# ece411_t2_schematic_FINAL.net
KiCad netlist of a schematic drawn in EAGLE
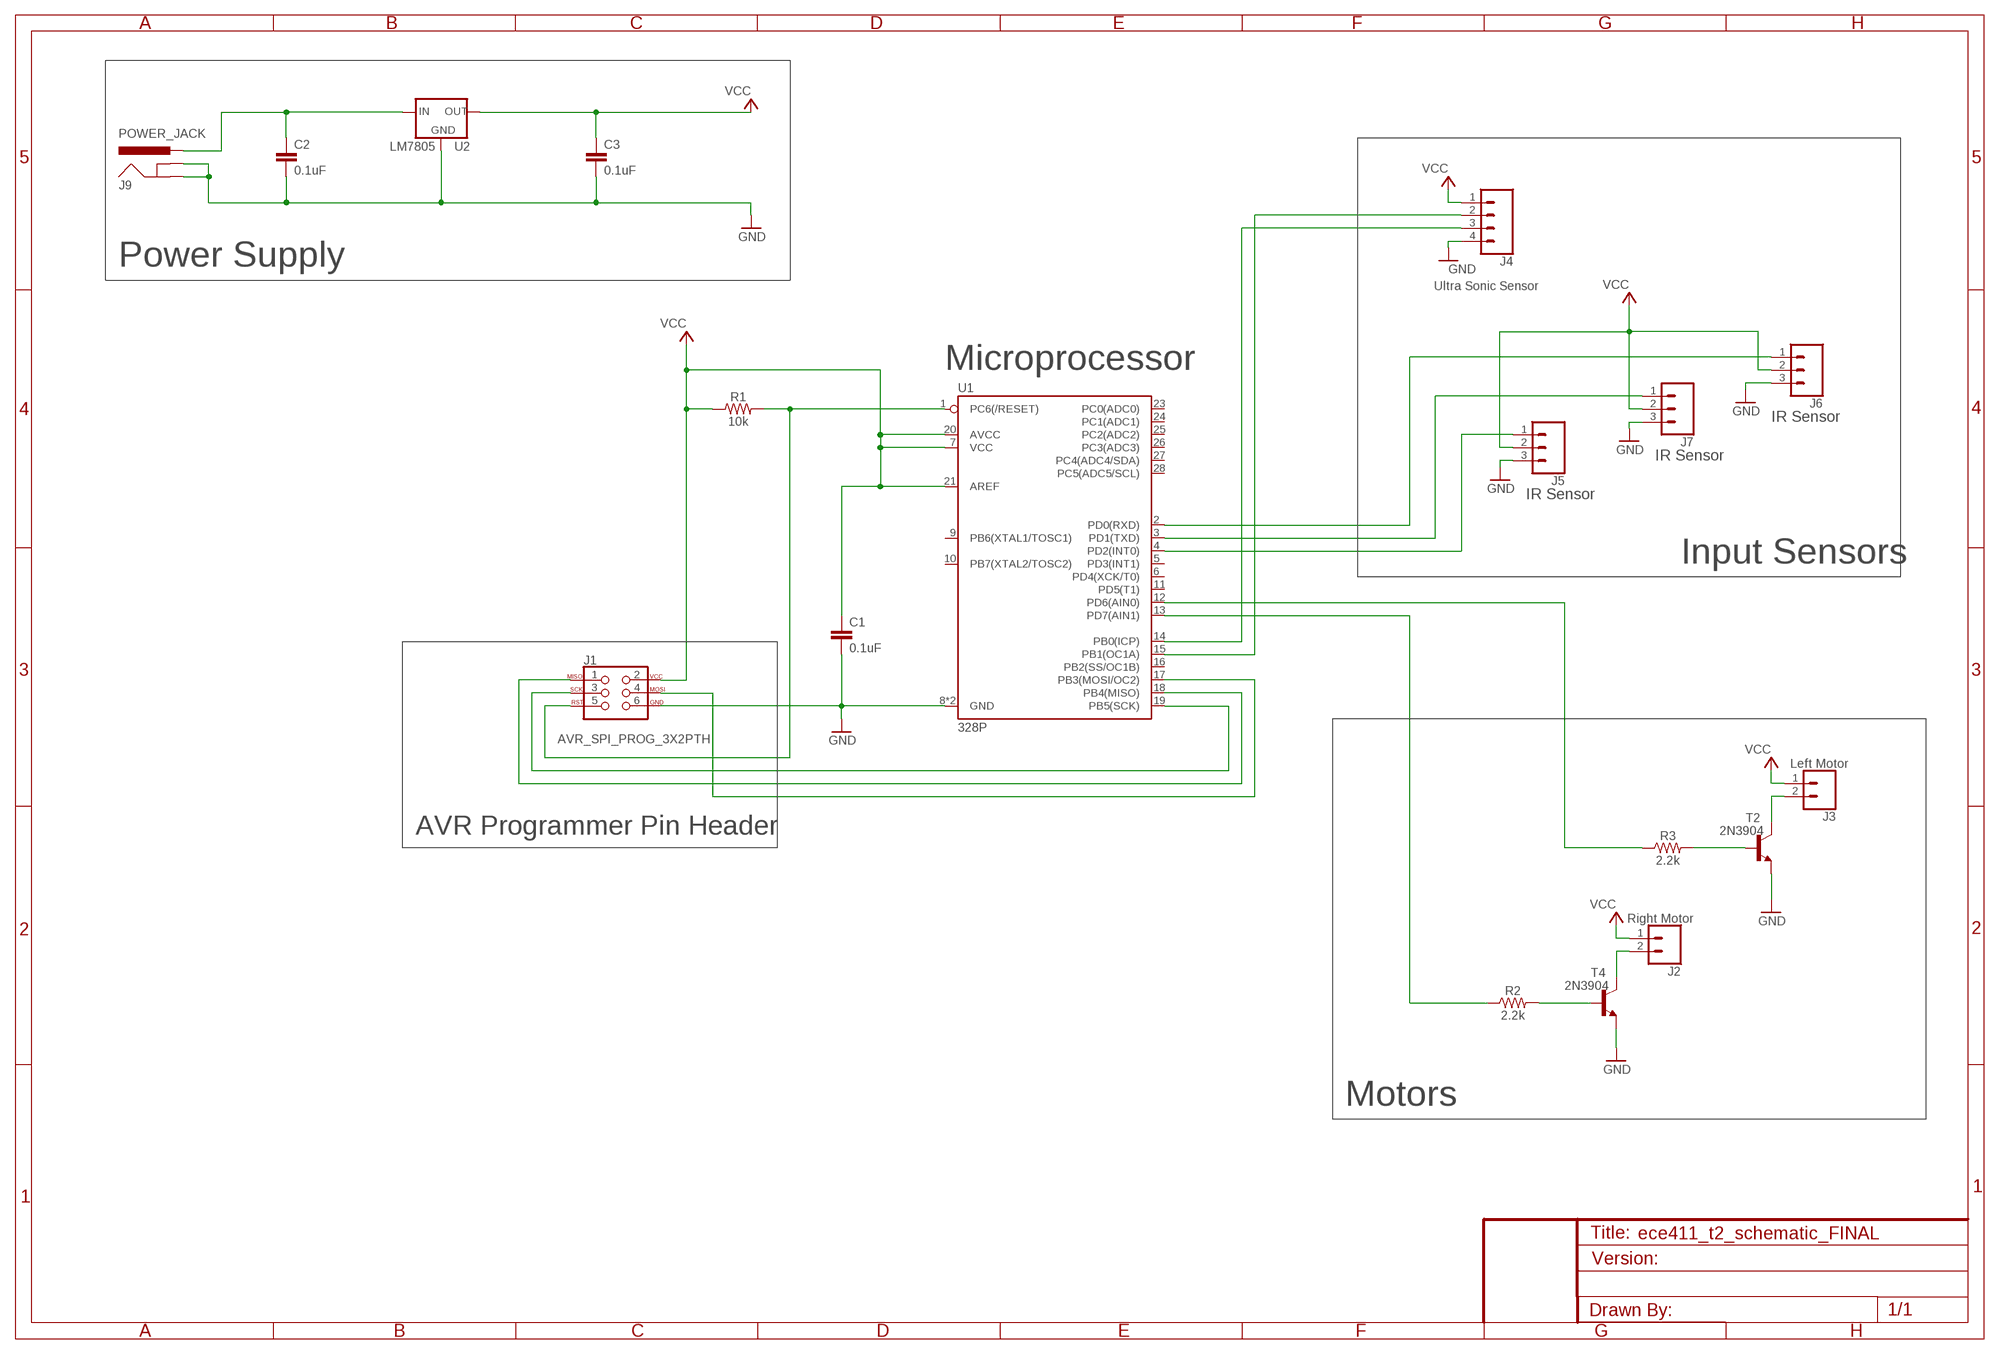
[diagram p0: schematic, sheet 1]

(export (version "E")
  (design (tool "Eeschema 10.0.6"))
  (components
    (comp (ref "C1")
      (value "0.1uF")
      (footprint "eagle-import:0402")
      (libsource (lib "eagle-import") (part "0.1UF-0402-6.3V-10%-X7R"))
    )
    (comp (ref "C2")
      (value "0.1uF")
      (footprint "eagle-import:0402")
      (libsource (lib "eagle-import") (part "0.1UF-0402-6.3V-10%-X7R"))
    )
    (comp (ref "C3")
      (value "0.1uF")
      (footprint "eagle-import:0402")
      (libsource (lib "eagle-import") (part "0.1UF-0402-6.3V-10%-X7R"))
    )
    (comp (ref "J1")
      (value "AVR_SPI_PROG_3X2PTH")
      (footprint "eagle-import:2X3")
      (libsource (lib "eagle-import") (part "AVR_SPI_PROG_3X2PTH"))
    )
    (comp (ref "J2")
      (value "Right Motor")
      (footprint "eagle-import:1X02")
      (libsource (lib "eagle-import") (part "CONN_02"))
    )
    (comp (ref "J3")
      (value "Left Motor")
      (footprint "eagle-import:1X02")
      (libsource (lib "eagle-import") (part "CONN_02"))
    )
    (comp (ref "J4")
      (value "Ultra Sonic Sensor")
      (footprint "eagle-import:1X04")
      (libsource (lib "eagle-import") (part "CONN_04"))
    )
    (comp (ref "J5")
      (value "455-1750-1-ND")
      (footprint "eagle-import:1X03")
      (libsource (lib "eagle-import") (part "CONN_03"))
    )
    (comp (ref "J6")
      (value "455-1750-1-ND")
      (footprint "eagle-import:1X03")
      (libsource (lib "eagle-import") (part "CONN_03"))
    )
    (comp (ref "J7")
      (value "455-1750-1-ND")
      (footprint "eagle-import:1X03")
      (libsource (lib "eagle-import") (part "CONN_03"))
    )
    (comp (ref "J9")
      (value "POWER_JACK")
      (footprint "eagle-import:POWER_JACK_PTH")
      (libsource (lib "eagle-import") (part "POWER_JACK"))
    )
    (comp (ref "R1")
      (value "10k")
      (footprint "eagle-import:0402")
      (libsource (lib "eagle-import") (part "10KOHM-0402-1/16W-1%"))
    )
    (comp (ref "R2")
      (value "2.2k")
      (footprint "eagle-import:0603")
      (libsource (lib "eagle-import") (part "2.2KOHM-0603-1/10W-1%"))
    )
    (comp (ref "R3")
      (value "2.2k")
      (footprint "eagle-import:0603")
      (libsource (lib "eagle-import") (part "2.2KOHM-0603-1/10W-1%"))
    )
    (comp (ref "T2")
      (value "2N3904")
      (footprint "eagle-import:TO92")
      (libsource (lib "eagle-import") (part "2N3904"))
    )
    (comp (ref "T4")
      (value "2N3904")
      (footprint "eagle-import:TO92")
      (libsource (lib "eagle-import") (part "2N3904"))
    )
    (comp (ref "U1")
      (value "328P")
      (footprint "eagle-import:DIP28")
      (libsource (lib "eagle-import") (part "ATMEGA328P_PDIP"))
    )
    (comp (ref "U2")
      (value "LM7805")
      (footprint "eagle-import:TO-220-ALT")
      (libsource (lib "eagle-import") (part "V_REG_78XX-TO-220"))
    )
  )
  (nets
    (net (code "1") (name "GND") (class "Default")
      (node (ref "C1") (pin "2") (pinfunction "2_2") (pintype "passive"))
      (node (ref "C2") (pin "2") (pinfunction "2_2") (pintype "passive"))
      (node (ref "C3") (pin "2") (pinfunction "2_2") (pintype "passive"))
      (node (ref "J1") (pin "6") (pinfunction "6_6") (pintype "passive"))
      (node (ref "J4") (pin "4") (pinfunction "4_4") (pintype "passive"))
      (node (ref "J5") (pin "3") (pinfunction "3_3") (pintype "passive"))
      (node (ref "J6") (pin "3") (pinfunction "3_3") (pintype "passive"))
      (node (ref "J7") (pin "3") (pinfunction "3_3") (pintype "passive"))
      (node (ref "J9") (pin "GND") (pinfunction "GND_GND") (pintype "bidirectional"))
      (node (ref "J9") (pin "GNDBREAK") (pinfunction "GNDBREAK_GNDBREAK") (pintype "bidirectional"))
      (node (ref "T2") (pin "3") (pinfunction "E_3") (pintype "passive"))
      (node (ref "T4") (pin "3") (pinfunction "E_3") (pintype "passive"))
      (node (ref "U1") (pin "22") (pinfunction "GND_22") (pintype "bidirectional"))
      (node (ref "U1") (pin "8") (pinfunction "GND_8") (pintype "bidirectional"))
      (node (ref "U2") (pin "GND") (pinfunction "GND_GND") (pintype "input"))
    )
    (net (code "2") (name "Net-(C2-Pad1)") (class "Default")
      (node (ref "C2") (pin "1") (pinfunction "1_1") (pintype "passive"))
      (node (ref "J9") (pin "PWR") (pinfunction "PWR_PWR") (pintype "bidirectional"))
      (node (ref "U2") (pin "IN") (pinfunction "IN_IN") (pintype "input"))
    )
    (net (code "3") (name "Net-(T2-B)") (class "Default")
      (node (ref "R3") (pin "2") (pinfunction "2_2") (pintype "passive"))
      (node (ref "T2") (pin "2") (pinfunction "B_2") (pintype "passive"))
    )
    (net (code "4") (name "Net-(T2-C)") (class "Default")
      (node (ref "J3") (pin "2") (pinfunction "2_2") (pintype "passive"))
      (node (ref "T2") (pin "1") (pinfunction "C_1") (pintype "passive"))
    )
    (net (code "5") (name "Net-(T4-B)") (class "Default")
      (node (ref "R2") (pin "2") (pinfunction "2_2") (pintype "passive"))
      (node (ref "T4") (pin "2") (pinfunction "B_2") (pintype "passive"))
    )
    (net (code "6") (name "Net-(T4-C)") (class "Default")
      (node (ref "J2") (pin "2") (pinfunction "2_2") (pintype "passive"))
      (node (ref "T4") (pin "1") (pinfunction "C_1") (pintype "passive"))
    )
    (net (code "7") (name "Net-(U1-PB0(ICP))") (class "Default")
      (node (ref "J4") (pin "3") (pinfunction "3_3") (pintype "passive"))
      (node (ref "U1") (pin "14") (pinfunction "PB0(ICP)_14") (pintype "bidirectional"))
    )
    (net (code "8") (name "Net-(U1-PB1(OC1A))") (class "Default")
      (node (ref "J4") (pin "2") (pinfunction "2_2") (pintype "passive"))
      (node (ref "U1") (pin "15") (pinfunction "PB1(OC1A)_15") (pintype "bidirectional"))
    )
    (net (code "9") (name "Net-(U1-PB3(MOSI{slash}OC2))") (class "Default")
      (node (ref "J1") (pin "4") (pinfunction "4_4") (pintype "passive"))
      (node (ref "U1") (pin "17") (pinfunction "PB3(MOSI/OC2)_17") (pintype "bidirectional"))
    )
    (net (code "10") (name "Net-(U1-PB4(MISO))") (class "Default")
      (node (ref "J1") (pin "1") (pinfunction "1_1") (pintype "passive"))
      (node (ref "U1") (pin "18") (pinfunction "PB4(MISO)_18") (pintype "bidirectional"))
    )
    (net (code "11") (name "Net-(U1-PB5(SCK))") (class "Default")
      (node (ref "J1") (pin "3") (pinfunction "3_3") (pintype "passive"))
      (node (ref "U1") (pin "19") (pinfunction "PB5(SCK)_19") (pintype "bidirectional"))
    )
    (net (code "12") (name "Net-(U1-PC6({slash}RESET))") (class "Default")
      (node (ref "J1") (pin "5") (pinfunction "5_5") (pintype "passive"))
      (node (ref "R1") (pin "2") (pinfunction "2_2") (pintype "passive"))
      (node (ref "U1") (pin "1") (pinfunction "PC6(/RESET)_1") (pintype "bidirectional"))
    )
    (net (code "13") (name "Net-(U1-PD0(RXD))") (class "Default")
      (node (ref "J6") (pin "1") (pinfunction "1_1") (pintype "passive"))
      (node (ref "U1") (pin "2") (pinfunction "PD0(RXD)_2") (pintype "bidirectional"))
    )
    (net (code "14") (name "Net-(U1-PD1(TXD))") (class "Default")
      (node (ref "J7") (pin "1") (pinfunction "1_1") (pintype "passive"))
      (node (ref "U1") (pin "3") (pinfunction "PD1(TXD)_3") (pintype "bidirectional"))
    )
    (net (code "15") (name "Net-(U1-PD2(INT0))") (class "Default")
      (node (ref "J5") (pin "1") (pinfunction "1_1") (pintype "passive"))
      (node (ref "U1") (pin "4") (pinfunction "PD2(INT0)_4") (pintype "bidirectional"))
    )
    (net (code "16") (name "Net-(U1-PD6(AIN0))") (class "Default")
      (node (ref "R3") (pin "1") (pinfunction "1_1") (pintype "passive"))
      (node (ref "U1") (pin "12") (pinfunction "PD6(AIN0)_12") (pintype "bidirectional"))
    )
    (net (code "17") (name "Net-(U1-PD7(AIN1))") (class "Default")
      (node (ref "R2") (pin "1") (pinfunction "1_1") (pintype "passive"))
      (node (ref "U1") (pin "13") (pinfunction "PD7(AIN1)_13") (pintype "bidirectional"))
    )
    (net (code "18") (name "VCC") (class "Default")
      (node (ref "C1") (pin "1") (pinfunction "1_1") (pintype "passive"))
      (node (ref "C3") (pin "1") (pinfunction "1_1") (pintype "passive"))
      (node (ref "J1") (pin "2") (pinfunction "2_2") (pintype "passive"))
      (node (ref "J2") (pin "1") (pinfunction "1_1") (pintype "passive"))
      (node (ref "J3") (pin "1") (pinfunction "1_1") (pintype "passive"))
      (node (ref "J4") (pin "1") (pinfunction "1_1") (pintype "passive"))
      (node (ref "J5") (pin "2") (pinfunction "2_2") (pintype "passive"))
      (node (ref "J6") (pin "2") (pinfunction "2_2") (pintype "passive"))
      (node (ref "J7") (pin "2") (pinfunction "2_2") (pintype "passive"))
      (node (ref "R1") (pin "1") (pinfunction "1_1") (pintype "passive"))
      (node (ref "U1") (pin "20") (pinfunction "AVCC_20") (pintype "bidirectional"))
      (node (ref "U1") (pin "21") (pinfunction "AREF_21") (pintype "bidirectional"))
      (node (ref "U1") (pin "7") (pinfunction "VCC_7") (pintype "bidirectional"))
      (node (ref "U2") (pin "OUT") (pinfunction "OUT_OUT") (pintype "passive"))
    )
    (net (code "19") (name "unconnected-(U1-PB2(SS{slash}OC1B)-Pad16)") (class "Default")
      (node (ref "U1") (pin "16") (pinfunction "PB2(SS/OC1B)_16") (pintype "bidirectional"))
    )
    (net (code "20") (name "unconnected-(U1-PB6(XTAL1{slash}TOSC1)-Pad9)") (class "Default")
      (node (ref "U1") (pin "9") (pinfunction "PB6(XTAL1/TOSC1)_9") (pintype "bidirectional"))
    )
    (net (code "21") (name "unconnected-(U1-PB7(XTAL2{slash}TOSC2)-Pad10)") (class "Default")
      (node (ref "U1") (pin "10") (pinfunction "PB7(XTAL2/TOSC2)_10") (pintype "bidirectional"))
    )
    (net (code "22") (name "unconnected-(U1-PC0(ADC0)-Pad23)") (class "Default")
      (node (ref "U1") (pin "23") (pinfunction "PC0(ADC0)_23") (pintype "bidirectional"))
    )
    (net (code "23") (name "unconnected-(U1-PC1(ADC1)-Pad24)") (class "Default")
      (node (ref "U1") (pin "24") (pinfunction "PC1(ADC1)_24") (pintype "bidirectional"))
    )
    (net (code "24") (name "unconnected-(U1-PC2(ADC2)-Pad25)") (class "Default")
      (node (ref "U1") (pin "25") (pinfunction "PC2(ADC2)_25") (pintype "bidirectional"))
    )
    (net (code "25") (name "unconnected-(U1-PC3(ADC3)-Pad26)") (class "Default")
      (node (ref "U1") (pin "26") (pinfunction "PC3(ADC3)_26") (pintype "bidirectional"))
    )
    (net (code "26") (name "unconnected-(U1-PC4(ADC4{slash}SDA)-Pad27)") (class "Default")
      (node (ref "U1") (pin "27") (pinfunction "PC4(ADC4/SDA)_27") (pintype "bidirectional"))
    )
    (net (code "27") (name "unconnected-(U1-PC5(ADC5{slash}SCL)-Pad28)") (class "Default")
      (node (ref "U1") (pin "28") (pinfunction "PC5(ADC5/SCL)_28") (pintype "bidirectional"))
    )
    (net (code "28") (name "unconnected-(U1-PD3(INT1)-Pad5)") (class "Default")
      (node (ref "U1") (pin "5") (pinfunction "PD3(INT1)_5") (pintype "bidirectional"))
    )
    (net (code "29") (name "unconnected-(U1-PD4(XCK{slash}T0)-Pad6)") (class "Default")
      (node (ref "U1") (pin "6") (pinfunction "PD4(XCK/T0)_6") (pintype "bidirectional"))
    )
    (net (code "30") (name "unconnected-(U1-PD5(T1)-Pad11)") (class "Default")
      (node (ref "U1") (pin "11") (pinfunction "PD5(T1)_11") (pintype "bidirectional"))
    )
  )
)
